# SendSlice.net
KiCad netlist of a schematic drawn in EAGLE
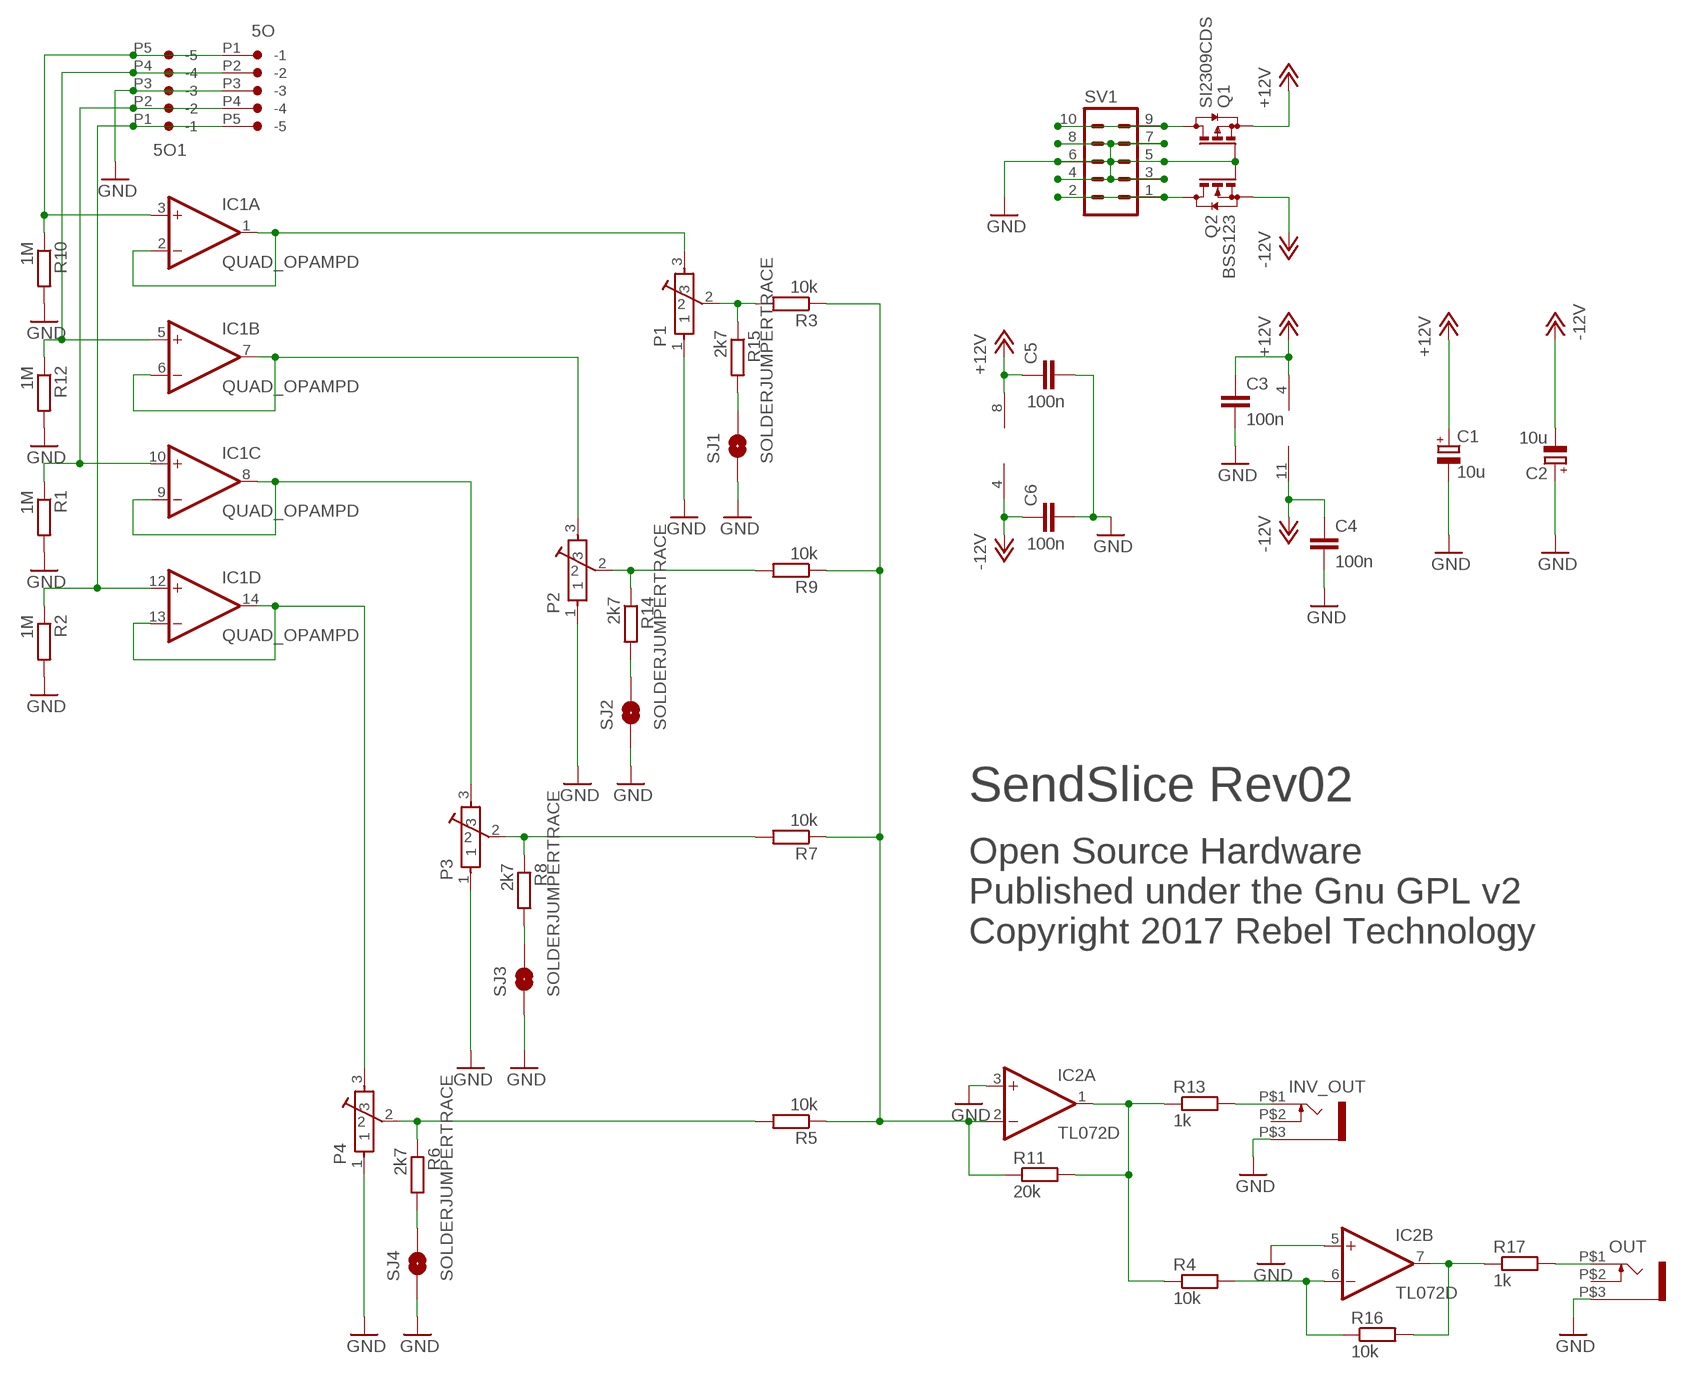
[diagram p0: schematic, sheet 1]

(export (version "E")
  (design (tool "Eeschema 10.0.6"))
  (components
    (comp (ref "5O")
      (value "CON-JST_PH_5W")
      (footprint "eagle-import:CON-JST_PH_5W")
      (libsource (lib "eagle-import") (part "CON-JST_PH_5W"))
    )
    (comp (ref "5O1")
      (value "CON-JST_PH_5W")
      (footprint "eagle-import:CON-JST_PH_5W")
      (libsource (lib "eagle-import") (part "CON-JST_PH_5W"))
    )
    (comp (ref "C1")
      (value "10u")
      (footprint "eagle-import:153CLV-0505")
      (libsource (lib "eagle-import") (part "CPOL-EU153CLV-0505"))
    )
    (comp (ref "C2")
      (value "10u")
      (footprint "eagle-import:153CLV-0505")
      (libsource (lib "eagle-import") (part "CPOL-EU153CLV-0505"))
    )
    (comp (ref "C3")
      (value "100n")
      (footprint "eagle-import:C0603")
      (libsource (lib "eagle-import") (part "C-EUC0603"))
    )
    (comp (ref "C4")
      (value "100n")
      (footprint "eagle-import:C0603")
      (libsource (lib "eagle-import") (part "C-EUC0603"))
    )
    (comp (ref "C5")
      (value "100n")
      (footprint "eagle-import:C0603")
      (libsource (lib "eagle-import") (part "C-EUC0603"))
    )
    (comp (ref "C6")
      (value "100n")
      (footprint "eagle-import:C0603")
      (libsource (lib "eagle-import") (part "C-EUC0603"))
    )
    (comp (ref "IC1")
      (value "QUAD_OPAMPD")
      (footprint "eagle-import:SO14")
      (libsource (lib "eagle-import") (part "QUAD_OPAMPD"))
    )
    (comp (ref "IC2")
      (value "TL072D")
      (footprint "eagle-import:SO08")
      (libsource (lib "eagle-import") (part "TL072D"))
    )
    (comp (ref "INV_OUT")
      (value "JACK-UJ-3502-R")
      (footprint "eagle-import:UJ-3502-R")
      (libsource (lib "eagle-import") (part "JACK-UJ-3502-R"))
    )
    (comp (ref "OUT")
      (value "JACK-UJ-3502-R")
      (footprint "eagle-import:UJ-3502-R")
      (libsource (lib "eagle-import") (part "JACK-UJ-3502-R"))
    )
    (comp (ref "P1")
      (value "10k lin")
      (footprint "eagle-import:POT-BOURNS-PTD901")
      (libsource (lib "eagle-import") (part "POT-BOURNS-PTD901"))
    )
    (comp (ref "P2")
      (value "10k lin")
      (footprint "eagle-import:POT-BOURNS-PTD901")
      (libsource (lib "eagle-import") (part "POT-BOURNS-PTD901"))
    )
    (comp (ref "P3")
      (value "10k lin")
      (footprint "eagle-import:POT-BOURNS-PTD901")
      (libsource (lib "eagle-import") (part "POT-BOURNS-PTD901"))
    )
    (comp (ref "P4")
      (value "10k lin")
      (footprint "eagle-import:POT-BOURNS-PTD901")
      (libsource (lib "eagle-import") (part "POT-BOURNS-PTD901"))
    )
    (comp (ref "Q1")
      (value "SI2309CDS")
      (footprint "eagle-import:SOT23")
      (libsource (lib "eagle-import") (part "BSS84"))
    )
    (comp (ref "Q2")
      (value "BSS123")
      (footprint "eagle-import:SOT23")
      (libsource (lib "eagle-import") (part "BSS123"))
    )
    (comp (ref "R1")
      (value "1M")
      (footprint "eagle-import:0603")
      (libsource (lib "eagle-import") (part "R-EU_0603"))
    )
    (comp (ref "R2")
      (value "1M")
      (footprint "eagle-import:0603")
      (libsource (lib "eagle-import") (part "R-EU_0603"))
    )
    (comp (ref "R3")
      (value "10k")
      (footprint "eagle-import:0603")
      (libsource (lib "eagle-import") (part "R-EU_0603"))
    )
    (comp (ref "R4")
      (value "10k")
      (footprint "eagle-import:0603")
      (libsource (lib "eagle-import") (part "R-EU_0603"))
    )
    (comp (ref "R5")
      (value "10k")
      (footprint "eagle-import:0603")
      (libsource (lib "eagle-import") (part "R-EU_0603"))
    )
    (comp (ref "R6")
      (value "2k7")
      (footprint "eagle-import:0603")
      (libsource (lib "eagle-import") (part "R-EU_0603"))
    )
    (comp (ref "R7")
      (value "10k")
      (footprint "eagle-import:0603")
      (libsource (lib "eagle-import") (part "R-EU_0603"))
    )
    (comp (ref "R8")
      (value "2k7")
      (footprint "eagle-import:0603")
      (libsource (lib "eagle-import") (part "R-EU_0603"))
    )
    (comp (ref "R9")
      (value "10k")
      (footprint "eagle-import:0603")
      (libsource (lib "eagle-import") (part "R-EU_0603"))
    )
    (comp (ref "R10")
      (value "1M")
      (footprint "eagle-import:0603")
      (libsource (lib "eagle-import") (part "R-EU_0603"))
    )
    (comp (ref "R11")
      (value "20k")
      (footprint "eagle-import:0603")
      (libsource (lib "eagle-import") (part "R-EU_0603"))
    )
    (comp (ref "R12")
      (value "1M")
      (footprint "eagle-import:0603")
      (libsource (lib "eagle-import") (part "R-EU_0603"))
    )
    (comp (ref "R13")
      (value "1k")
      (footprint "eagle-import:0603")
      (libsource (lib "eagle-import") (part "R-EU_0603"))
    )
    (comp (ref "R14")
      (value "2k7")
      (footprint "eagle-import:0603")
      (libsource (lib "eagle-import") (part "R-EU_0603"))
    )
    (comp (ref "R15")
      (value "2k7")
      (footprint "eagle-import:0603")
      (libsource (lib "eagle-import") (part "R-EU_0603"))
    )
    (comp (ref "R16")
      (value "10k")
      (footprint "eagle-import:0603")
      (libsource (lib "eagle-import") (part "R-EU_0603"))
    )
    (comp (ref "R17")
      (value "1k")
      (footprint "eagle-import:0603")
      (libsource (lib "eagle-import") (part "R-EU_0603"))
    )
    (comp (ref "SJ1")
      (value "SOLDERJUMPERTRACE")
      (footprint "eagle-import:SJ_2S-TRACE")
      (libsource (lib "eagle-import") (part "SOLDERJUMPERTRACE"))
    )
    (comp (ref "SJ2")
      (value "SOLDERJUMPERTRACE")
      (footprint "eagle-import:SJ_2S-TRACE")
      (libsource (lib "eagle-import") (part "SOLDERJUMPERTRACE"))
    )
    (comp (ref "SJ3")
      (value "SOLDERJUMPERTRACE")
      (footprint "eagle-import:SJ_2S-TRACE")
      (libsource (lib "eagle-import") (part "SOLDERJUMPERTRACE"))
    )
    (comp (ref "SJ4")
      (value "SOLDERJUMPERTRACE")
      (footprint "eagle-import:SJ_2S-TRACE")
      (libsource (lib "eagle-import") (part "SOLDERJUMPERTRACE"))
    )
    (comp (ref "SV1")
      (value "MA05-2")
      (footprint "eagle-import:MA05-2")
      (libsource (lib "eagle-import") (part "MA05-2"))
    )
  )
  (nets
    (net (code "1") (name "+12V") (class "Default")
      (node (ref "C1") (pin "+") (pinfunction "+_+") (pintype "passive"))
      (node (ref "C3") (pin "1") (pinfunction "1_1") (pintype "passive"))
      (node (ref "C5") (pin "1") (pinfunction "1_1") (pintype "passive"))
      (node (ref "IC1") (pin "4") (pinfunction "V+_4") (pintype "power_in"))
      (node (ref "IC2") (pin "8") (pinfunction "V+_8") (pintype "power_in"))
      (node (ref "Q1") (pin "2") (pinfunction "S_2") (pintype "passive"))
    )
    (net (code "2") (name "-12V") (class "Default")
      (node (ref "C2") (pin "-") (pinfunction "-_-") (pintype "passive"))
      (node (ref "C4") (pin "1") (pinfunction "1_1") (pintype "passive"))
      (node (ref "C6") (pin "1") (pinfunction "1_1") (pintype "passive"))
      (node (ref "IC1") (pin "11") (pinfunction "V-_11") (pintype "power_in"))
      (node (ref "IC2") (pin "4") (pinfunction "V-_4") (pintype "power_in"))
      (node (ref "Q2") (pin "2") (pinfunction "S_2") (pintype "passive"))
    )
    (net (code "3") (name "GND") (class "Default")
      (node (ref "5O") (pin "P3") (pinfunction "-3_P3") (pintype "bidirectional"))
      (node (ref "5O1") (pin "P3") (pinfunction "-3_P3") (pintype "bidirectional"))
      (node (ref "C1") (pin "-") (pinfunction "-_-") (pintype "passive"))
      (node (ref "C2") (pin "+") (pinfunction "+_+") (pintype "passive"))
      (node (ref "C3") (pin "2") (pinfunction "2_2") (pintype "passive"))
      (node (ref "C4") (pin "2") (pinfunction "2_2") (pintype "passive"))
      (node (ref "C5") (pin "2") (pinfunction "2_2") (pintype "passive"))
      (node (ref "C6") (pin "2") (pinfunction "2_2") (pintype "passive"))
      (node (ref "IC2") (pin "3") (pinfunction "+IN_3") (pintype "input"))
      (node (ref "IC2") (pin "5") (pinfunction "+IN_5") (pintype "input"))
      (node (ref "INV_OUT") (pin "P$3") (pinfunction "SLEEVE_P$3") (pintype "passive"))
      (node (ref "OUT") (pin "P$3") (pinfunction "SLEEVE_P$3") (pintype "passive"))
      (node (ref "P1") (pin "1") (pinfunction "1_1") (pintype "bidirectional"))
      (node (ref "P2") (pin "1") (pinfunction "1_1") (pintype "bidirectional"))
      (node (ref "P3") (pin "1") (pinfunction "1_1") (pintype "bidirectional"))
      (node (ref "P4") (pin "1") (pinfunction "1_1") (pintype "bidirectional"))
      (node (ref "Q1") (pin "1") (pinfunction "G_1") (pintype "passive"))
      (node (ref "Q2") (pin "1") (pinfunction "G_1") (pintype "passive"))
      (node (ref "R1") (pin "2") (pinfunction "2_2") (pintype "passive"))
      (node (ref "R10") (pin "2") (pinfunction "2_2") (pintype "passive"))
      (node (ref "R12") (pin "2") (pinfunction "2_2") (pintype "passive"))
      (node (ref "R2") (pin "2") (pinfunction "2_2") (pintype "passive"))
      (node (ref "SJ1") (pin "1") (pinfunction "1_1") (pintype "passive"))
      (node (ref "SJ2") (pin "1") (pinfunction "1_1") (pintype "passive"))
      (node (ref "SJ3") (pin "1") (pinfunction "1_1") (pintype "passive"))
      (node (ref "SJ4") (pin "1") (pinfunction "1_1") (pintype "passive"))
      (node (ref "SV1") (pin "3") (pinfunction "3_3") (pintype "passive"))
      (node (ref "SV1") (pin "4") (pinfunction "4_4") (pintype "passive"))
      (node (ref "SV1") (pin "5") (pinfunction "5_5") (pintype "passive"))
      (node (ref "SV1") (pin "6") (pinfunction "6_6") (pintype "passive"))
      (node (ref "SV1") (pin "7") (pinfunction "7_7") (pintype "passive"))
      (node (ref "SV1") (pin "8") (pinfunction "8_8") (pintype "passive"))
    )
    (net (code "4") (name "Net-(5O--1)") (class "Default")
      (node (ref "5O") (pin "P1") (pinfunction "-1_P1") (pintype "bidirectional"))
      (node (ref "5O1") (pin "P5") (pinfunction "-5_P5") (pintype "bidirectional"))
      (node (ref "IC1") (pin "3") (pinfunction "+IN_3") (pintype "input"))
      (node (ref "R10") (pin "1") (pinfunction "1_1") (pintype "passive"))
    )
    (net (code "5") (name "Net-(5O--2)") (class "Default")
      (node (ref "5O") (pin "P2") (pinfunction "-2_P2") (pintype "bidirectional"))
      (node (ref "5O1") (pin "P4") (pinfunction "-4_P4") (pintype "bidirectional"))
      (node (ref "IC1") (pin "5") (pinfunction "+IN_5") (pintype "input"))
      (node (ref "R12") (pin "1") (pinfunction "1_1") (pintype "passive"))
    )
    (net (code "6") (name "Net-(5O--4)") (class "Default")
      (node (ref "5O") (pin "P4") (pinfunction "-4_P4") (pintype "bidirectional"))
      (node (ref "5O1") (pin "P2") (pinfunction "-2_P2") (pintype "bidirectional"))
      (node (ref "IC1") (pin "10") (pinfunction "+IN_10") (pintype "input"))
      (node (ref "R1") (pin "1") (pinfunction "1_1") (pintype "passive"))
    )
    (net (code "7") (name "Net-(5O--5)") (class "Default")
      (node (ref "5O") (pin "P5") (pinfunction "-5_P5") (pintype "bidirectional"))
      (node (ref "5O1") (pin "P1") (pinfunction "-1_P1") (pintype "bidirectional"))
      (node (ref "IC1") (pin "12") (pinfunction "+IN_12") (pintype "input"))
      (node (ref "R2") (pin "1") (pinfunction "1_1") (pintype "passive"))
    )
    (net (code "8") (name "Net-(IC1A--IN)") (class "Default")
      (node (ref "IC1") (pin "1") (pinfunction "OUT_1") (pintype "output"))
      (node (ref "IC1") (pin "2") (pinfunction "-IN_2") (pintype "input"))
      (node (ref "P1") (pin "3") (pinfunction "3_3") (pintype "bidirectional"))
    )
    (net (code "9") (name "Net-(IC1B--IN)") (class "Default")
      (node (ref "IC1") (pin "6") (pinfunction "-IN_6") (pintype "input"))
      (node (ref "IC1") (pin "7") (pinfunction "OUT_7") (pintype "output"))
      (node (ref "P2") (pin "3") (pinfunction "3_3") (pintype "bidirectional"))
    )
    (net (code "10") (name "Net-(IC1C--IN)") (class "Default")
      (node (ref "IC1") (pin "8") (pinfunction "OUT_8") (pintype "output"))
      (node (ref "IC1") (pin "9") (pinfunction "-IN_9") (pintype "input"))
      (node (ref "P3") (pin "3") (pinfunction "3_3") (pintype "bidirectional"))
    )
    (net (code "11") (name "Net-(IC1D--IN)") (class "Default")
      (node (ref "IC1") (pin "13") (pinfunction "-IN_13") (pintype "input"))
      (node (ref "IC1") (pin "14") (pinfunction "OUT_14") (pintype "output"))
      (node (ref "P4") (pin "3") (pinfunction "3_3") (pintype "bidirectional"))
    )
    (net (code "12") (name "Net-(IC2A--IN)") (class "Default")
      (node (ref "IC2") (pin "2") (pinfunction "-IN_2") (pintype "input"))
      (node (ref "R11") (pin "1") (pinfunction "1_1") (pintype "passive"))
      (node (ref "R3") (pin "1") (pinfunction "1_1") (pintype "passive"))
      (node (ref "R5") (pin "1") (pinfunction "1_1") (pintype "passive"))
      (node (ref "R7") (pin "1") (pinfunction "1_1") (pintype "passive"))
      (node (ref "R9") (pin "1") (pinfunction "1_1") (pintype "passive"))
    )
    (net (code "13") (name "Net-(IC2A-OUT)") (class "Default")
      (node (ref "IC2") (pin "1") (pinfunction "OUT_1") (pintype "output"))
      (node (ref "R11") (pin "2") (pinfunction "2_2") (pintype "passive"))
      (node (ref "R13") (pin "1") (pinfunction "1_1") (pintype "passive"))
      (node (ref "R4") (pin "1") (pinfunction "1_1") (pintype "passive"))
    )
    (net (code "14") (name "Net-(IC2B--IN)") (class "Default")
      (node (ref "IC2") (pin "6") (pinfunction "-IN_6") (pintype "input"))
      (node (ref "R16") (pin "1") (pinfunction "1_1") (pintype "passive"))
      (node (ref "R4") (pin "2") (pinfunction "2_2") (pintype "passive"))
    )
    (net (code "15") (name "Net-(IC2B-OUT)") (class "Default")
      (node (ref "IC2") (pin "7") (pinfunction "OUT_7") (pintype "output"))
      (node (ref "R16") (pin "2") (pinfunction "2_2") (pintype "passive"))
      (node (ref "R17") (pin "1") (pinfunction "1_1") (pintype "passive"))
    )
    (net (code "16") (name "Net-(INV_OUT-TIP)") (class "Default")
      (node (ref "INV_OUT") (pin "P$1") (pinfunction "TIP_P$1") (pintype "passive"))
      (node (ref "R13") (pin "2") (pinfunction "2_2") (pintype "passive"))
    )
    (net (code "17") (name "Net-(OUT-TIP)") (class "Default")
      (node (ref "OUT") (pin "P$1") (pinfunction "TIP_P$1") (pintype "passive"))
      (node (ref "R17") (pin "2") (pinfunction "2_2") (pintype "passive"))
    )
    (net (code "18") (name "Net-(P1-Pad2)") (class "Default")
      (node (ref "P1") (pin "2") (pinfunction "2_2") (pintype "bidirectional"))
      (node (ref "R15") (pin "1") (pinfunction "1_1") (pintype "passive"))
      (node (ref "R3") (pin "2") (pinfunction "2_2") (pintype "passive"))
    )
    (net (code "19") (name "Net-(P2-Pad2)") (class "Default")
      (node (ref "P2") (pin "2") (pinfunction "2_2") (pintype "bidirectional"))
      (node (ref "R14") (pin "1") (pinfunction "1_1") (pintype "passive"))
      (node (ref "R9") (pin "2") (pinfunction "2_2") (pintype "passive"))
    )
    (net (code "20") (name "Net-(P3-Pad2)") (class "Default")
      (node (ref "P3") (pin "2") (pinfunction "2_2") (pintype "bidirectional"))
      (node (ref "R7") (pin "2") (pinfunction "2_2") (pintype "passive"))
      (node (ref "R8") (pin "1") (pinfunction "1_1") (pintype "passive"))
    )
    (net (code "21") (name "Net-(P4-Pad2)") (class "Default")
      (node (ref "P4") (pin "2") (pinfunction "2_2") (pintype "bidirectional"))
      (node (ref "R5") (pin "2") (pinfunction "2_2") (pintype "passive"))
      (node (ref "R6") (pin "1") (pinfunction "1_1") (pintype "passive"))
    )
    (net (code "22") (name "Net-(Q1-D)") (class "Default")
      (node (ref "Q1") (pin "3") (pinfunction "D_3") (pintype "passive"))
      (node (ref "SV1") (pin "10") (pinfunction "10_10") (pintype "passive"))
      (node (ref "SV1") (pin "9") (pinfunction "9_9") (pintype "passive"))
    )
    (net (code "23") (name "Net-(Q2-D)") (class "Default")
      (node (ref "Q2") (pin "3") (pinfunction "D_3") (pintype "passive"))
      (node (ref "SV1") (pin "1") (pinfunction "1_1") (pintype "passive"))
      (node (ref "SV1") (pin "2") (pinfunction "2_2") (pintype "passive"))
    )
    (net (code "24") (name "Net-(R6-Pad2)") (class "Default")
      (node (ref "R6") (pin "2") (pinfunction "2_2") (pintype "passive"))
      (node (ref "SJ4") (pin "2") (pinfunction "2_2") (pintype "passive"))
    )
    (net (code "25") (name "Net-(R8-Pad2)") (class "Default")
      (node (ref "R8") (pin "2") (pinfunction "2_2") (pintype "passive"))
      (node (ref "SJ3") (pin "2") (pinfunction "2_2") (pintype "passive"))
    )
    (net (code "26") (name "Net-(R14-Pad2)") (class "Default")
      (node (ref "R14") (pin "2") (pinfunction "2_2") (pintype "passive"))
      (node (ref "SJ2") (pin "2") (pinfunction "2_2") (pintype "passive"))
    )
    (net (code "27") (name "Net-(R15-Pad2)") (class "Default")
      (node (ref "R15") (pin "2") (pinfunction "2_2") (pintype "passive"))
      (node (ref "SJ1") (pin "2") (pinfunction "2_2") (pintype "passive"))
    )
    (net (code "28") (name "unconnected-(INV_OUT-SW-PadP$2)") (class "Default")
      (node (ref "INV_OUT") (pin "P$2") (pinfunction "SW_P$2") (pintype "passive"))
    )
    (net (code "29") (name "unconnected-(OUT-SW-PadP$2)") (class "Default")
      (node (ref "OUT") (pin "P$2") (pinfunction "SW_P$2") (pintype "passive"))
    )
  )
)
